# bldcshield.net
KiCad netlist of a schematic drawn in EAGLE
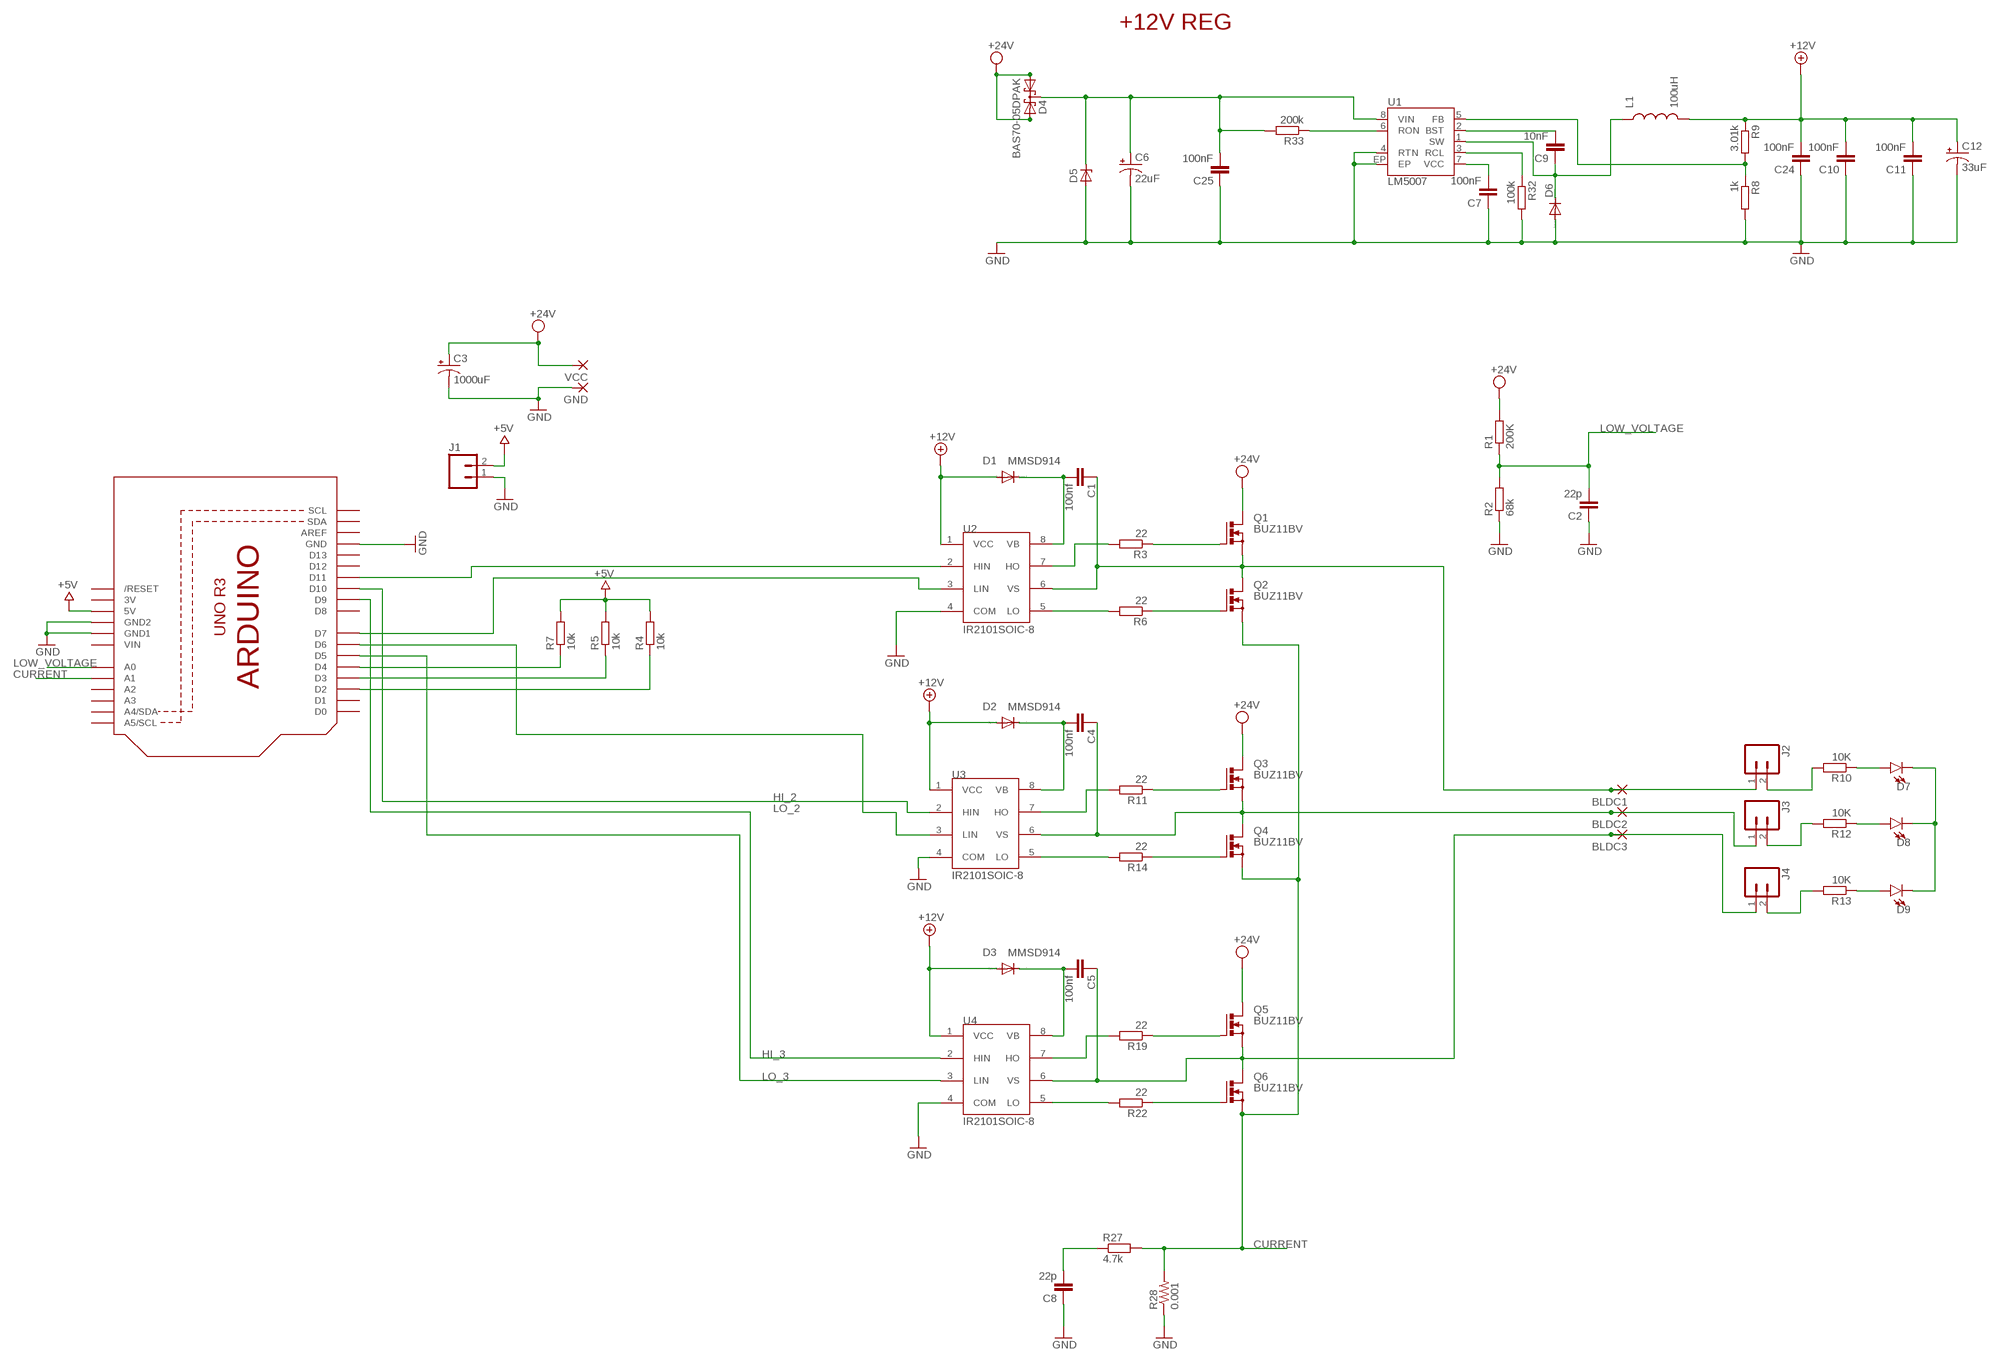
[diagram p0: schematic, sheet 1]

(export (version "E")
  (design (tool "Eeschema 10.0.6"))
  (components
    (comp (ref "BLDC1")
      (value "WIREPAD4,16O1,6")
      (footprint "eagle-import:4,16O1,6")
      (libsource (lib "eagle-import") (part "WIREPAD4,16O1,6"))
    )
    (comp (ref "BLDC2")
      (value "WIREPAD4,16O1,6")
      (footprint "eagle-import:4,16O1,6")
      (libsource (lib "eagle-import") (part "WIREPAD4,16O1,6"))
    )
    (comp (ref "BLDC3")
      (value "WIREPAD4,16O1,6")
      (footprint "eagle-import:4,16O1,6")
      (libsource (lib "eagle-import") (part "WIREPAD4,16O1,6"))
    )
    (comp (ref "C1")
      (value "100nf")
      (footprint "eagle-import:C1206")
      (libsource (lib "eagle-import") (part "C-EUC1206"))
    )
    (comp (ref "C2")
      (value "22p")
      (footprint "eagle-import:C1206")
      (libsource (lib "eagle-import") (part "C-EUC1206"))
    )
    (comp (ref "C3")
      (value "1000uF")
      (footprint "eagle-import:CPOL-RADIAL-1000UF-63V")
      (libsource (lib "eagle-import") (part "CAP_POLPTH3"))
    )
    (comp (ref "C4")
      (value "100nf")
      (footprint "eagle-import:C1206")
      (libsource (lib "eagle-import") (part "C-EUC1206"))
    )
    (comp (ref "C5")
      (value "100nf")
      (footprint "eagle-import:C1206")
      (libsource (lib "eagle-import") (part "C-EUC1206"))
    )
    (comp (ref "C6")
      (value "22uF")
      (footprint "eagle-import:PANASONIC_C")
      (libsource (lib "eagle-import") (part "22UF-POLAR-PANASONIC_C-35V-20%"))
    )
    (comp (ref "C7")
      (value "100nF")
      (footprint "eagle-import:C1206")
      (libsource (lib "eagle-import") (part "C-EUC1206"))
    )
    (comp (ref "C8")
      (value "22p")
      (footprint "eagle-import:C1206")
      (libsource (lib "eagle-import") (part "C-EUC1206"))
    )
    (comp (ref "C9")
      (value "10nF")
      (footprint "eagle-import:C1206")
      (libsource (lib "eagle-import") (part "C-EUC1206"))
    )
    (comp (ref "C10")
      (value "100nF")
      (footprint "eagle-import:C1206")
      (libsource (lib "eagle-import") (part "C-EUC1206"))
    )
    (comp (ref "C11")
      (value "100nF")
      (footprint "eagle-import:C1206")
      (libsource (lib "eagle-import") (part "C-EUC1206"))
    )
    (comp (ref "C12")
      (value "33uF")
      (footprint "eagle-import:PANASONIC_C")
      (libsource (lib "eagle-import") (part "22UF-POLAR-PANASONIC_C-35V-20%"))
    )
    (comp (ref "C24")
      (value "100nF")
      (footprint "eagle-import:C1206")
      (libsource (lib "eagle-import") (part "C-EUC1206"))
    )
    (comp (ref "C25")
      (value "100nF")
      (footprint "eagle-import:C1206")
      (libsource (lib "eagle-import") (part "C-EUC1206"))
    )
    (comp (ref "D1")
      (value "MMSD914")
      (footprint "eagle-import:SOD123")
      (libsource (lib "eagle-import") (part "DIODE-SOD123"))
    )
    (comp (ref "D2")
      (value "MMSD914")
      (footprint "eagle-import:SOD123")
      (libsource (lib "eagle-import") (part "DIODE-SOD123"))
    )
    (comp (ref "D3")
      (value "MMSD914")
      (footprint "eagle-import:SOD123")
      (libsource (lib "eagle-import") (part "DIODE-SOD123"))
    )
    (comp (ref "D4")
      (value "BAS70-05DPAK")
      (footprint "eagle-import:DPAK229P990X238-3N")
      (libsource (lib "eagle-import") (part "BAS70-05DPAK"))
    )
    (comp (ref "D5")
      (value "SMF43A")
      (footprint "eagle-import:SOD123F")
      (fields (field (name "MF") "Littelfuse"))
      (libsource (lib "eagle-import") (part "SMFA43"))
    )
    (comp (ref "D6")
      (value "MBR0520LT")
      (footprint "eagle-import:SOD123")
      (libsource (lib "eagle-import") (part "MBR0520LT"))
    )
    (comp (ref "D7")
      (value "LED5MM")
      (footprint "eagle-import:LED_5MM")
      (libsource (lib "eagle-import") (part "LED5MM"))
    )
    (comp (ref "D8")
      (value "LED5MM")
      (footprint "eagle-import:LED_5MM")
      (libsource (lib "eagle-import") (part "LED5MM"))
    )
    (comp (ref "D9")
      (value "LED5MM")
      (footprint "eagle-import:LED_5MM")
      (libsource (lib "eagle-import") (part "LED5MM"))
    )
    (comp (ref "GND")
      (value "WIREPAD4,16O1,6")
      (footprint "eagle-import:4,16O1,6")
      (libsource (lib "eagle-import") (part "WIREPAD4,16O1,6"))
    )
    (comp (ref "J1")
      (value "M02PTH")
      (footprint "eagle-import:1X02")
      (libsource (lib "eagle-import") (part "M02PTH"))
    )
    (comp (ref "J2")
      (value "M02PTH")
      (footprint "eagle-import:1X02")
      (libsource (lib "eagle-import") (part "M02PTH"))
    )
    (comp (ref "J3")
      (value "M02PTH")
      (footprint "eagle-import:1X02")
      (libsource (lib "eagle-import") (part "M02PTH"))
    )
    (comp (ref "J4")
      (value "M02PTH")
      (footprint "eagle-import:1X02")
      (libsource (lib "eagle-import") (part "M02PTH"))
    )
    (comp (ref "L1")
      (value "100uH")
      (footprint "eagle-import:INDUCTOR-SRP4020")
      (libsource (lib "eagle-import") (part "INDUCTOR"))
    )
    (comp (ref "Q1")
      (value "BUZ11BV")
      (footprint "eagle-import:TO220BV")
      (libsource (lib "eagle-import") (part "BUZ11BV"))
    )
    (comp (ref "Q2")
      (value "BUZ11BV")
      (footprint "eagle-import:TO220BV")
      (libsource (lib "eagle-import") (part "BUZ11BV"))
    )
    (comp (ref "Q3")
      (value "BUZ11BV")
      (footprint "eagle-import:TO220BV")
      (libsource (lib "eagle-import") (part "BUZ11BV"))
    )
    (comp (ref "Q4")
      (value "BUZ11BV")
      (footprint "eagle-import:TO220BV")
      (libsource (lib "eagle-import") (part "BUZ11BV"))
    )
    (comp (ref "Q5")
      (value "BUZ11BV")
      (footprint "eagle-import:TO220BV")
      (libsource (lib "eagle-import") (part "BUZ11BV"))
    )
    (comp (ref "Q6")
      (value "BUZ11BV")
      (footprint "eagle-import:TO220BV")
      (libsource (lib "eagle-import") (part "BUZ11BV"))
    )
    (comp (ref "Q8")
      (value "Shield")
      (footprint "eagle-import:ARDUINOR3-NOTEXT-NOIOREF")
      (libsource (lib "eagle-import") (part "ARDUINOR3-NOIOREF-NOTEXT"))
    )
    (comp (ref "R1")
      (value "200K")
      (footprint "eagle-import:R1206")
      (libsource (lib "eagle-import") (part "R-EU_R1206"))
    )
    (comp (ref "R2")
      (value "68k")
      (footprint "eagle-import:R1206")
      (libsource (lib "eagle-import") (part "R-EU_R1206"))
    )
    (comp (ref "R3")
      (value "22")
      (footprint "eagle-import:R1206")
      (libsource (lib "eagle-import") (part "R-EU_R1206"))
    )
    (comp (ref "R4")
      (value "10k")
      (footprint "eagle-import:R1206")
      (libsource (lib "eagle-import") (part "R-EU_R1206"))
    )
    (comp (ref "R5")
      (value "10k")
      (footprint "eagle-import:R1206")
      (libsource (lib "eagle-import") (part "R-EU_R1206"))
    )
    (comp (ref "R6")
      (value "22")
      (footprint "eagle-import:R1206")
      (libsource (lib "eagle-import") (part "R-EU_R1206"))
    )
    (comp (ref "R7")
      (value "10k")
      (footprint "eagle-import:R1206")
      (libsource (lib "eagle-import") (part "R-EU_R1206"))
    )
    (comp (ref "R8")
      (value "1k")
      (footprint "eagle-import:R1206")
      (libsource (lib "eagle-import") (part "R-EU_R1206"))
    )
    (comp (ref "R9")
      (value "3.01k")
      (footprint "eagle-import:R1206")
      (libsource (lib "eagle-import") (part "R-EU_R1206"))
    )
    (comp (ref "R10")
      (value "10K")
      (footprint "eagle-import:R1206")
      (libsource (lib "eagle-import") (part "R-EU_R1206"))
    )
    (comp (ref "R11")
      (value "22")
      (footprint "eagle-import:R1206")
      (libsource (lib "eagle-import") (part "R-EU_R1206"))
    )
    (comp (ref "R12")
      (value "10K")
      (footprint "eagle-import:R1206")
      (libsource (lib "eagle-import") (part "R-EU_R1206"))
    )
    (comp (ref "R13")
      (value "10K")
      (footprint "eagle-import:R1206")
      (libsource (lib "eagle-import") (part "R-EU_R1206"))
    )
    (comp (ref "R14")
      (value "22")
      (footprint "eagle-import:R1206")
      (libsource (lib "eagle-import") (part "R-EU_R1206"))
    )
    (comp (ref "R19")
      (value "22")
      (footprint "eagle-import:R1206")
      (libsource (lib "eagle-import") (part "R-EU_R1206"))
    )
    (comp (ref "R22")
      (value "22")
      (footprint "eagle-import:R1206")
      (libsource (lib "eagle-import") (part "R-EU_R1206"))
    )
    (comp (ref "R27")
      (value "4.7k")
      (footprint "eagle-import:R1206")
      (libsource (lib "eagle-import") (part "R-EU_R1206"))
    )
    (comp (ref "R28")
      (value "0.001")
      (footprint "eagle-import:R2512")
      (libsource (lib "eagle-import") (part "R-US_R2512"))
    )
    (comp (ref "R32")
      (value "100k")
      (footprint "eagle-import:R1206")
      (libsource (lib "eagle-import") (part "R-EU_R1206"))
    )
    (comp (ref "R33")
      (value "200k")
      (footprint "eagle-import:R1206")
      (libsource (lib "eagle-import") (part "R-EU_R1206"))
    )
    (comp (ref "U1")
      (value "LM5007")
      (footprint "eagle-import:MSOP-8-EP")
      (libsource (lib "eagle-import") (part "LM5007"))
    )
    (comp (ref "U2")
      (value "IR2101SOIC-8")
      (footprint "eagle-import:SOIC127P490X600X175-8N")
      (libsource (lib "eagle-import") (part "IR2101SOIC-8"))
    )
    (comp (ref "U3")
      (value "IR2101SOIC-8")
      (footprint "eagle-import:SOIC127P490X600X175-8N")
      (libsource (lib "eagle-import") (part "IR2101SOIC-8"))
    )
    (comp (ref "U4")
      (value "IR2101SOIC-8")
      (footprint "eagle-import:SOIC127P490X600X175-8N")
      (libsource (lib "eagle-import") (part "IR2101SOIC-8"))
    )
    (comp (ref "VCC")
      (value "WIREPAD4,16O1,6")
      (footprint "eagle-import:4,16O1,6")
      (libsource (lib "eagle-import") (part "WIREPAD4,16O1,6"))
    )
  )
  (nets
    (net (code "1") (name "+5V") (class "Default")
      (node (ref "J1") (pin "2") (pinfunction "2_2") (pintype "passive"))
      (node (ref "Q8") (pin "5V") (pinfunction "5V_5V") (pintype "power_in"))
      (node (ref "R4") (pin "2") (pinfunction "2_2") (pintype "passive"))
      (node (ref "R5") (pin "2") (pinfunction "2_2") (pintype "passive"))
      (node (ref "R7") (pin "2") (pinfunction "2_2") (pintype "passive"))
    )
    (net (code "2") (name "+12V") (class "Default")
      (node (ref "C10") (pin "2") (pinfunction "2_2") (pintype "passive"))
      (node (ref "C11") (pin "2") (pinfunction "2_2") (pintype "passive"))
      (node (ref "C12") (pin "+") (pinfunction "+_+") (pintype "passive"))
      (node (ref "C24") (pin "2") (pinfunction "2_2") (pintype "passive"))
      (node (ref "D1") (pin "A") (pinfunction "A_A") (pintype "passive"))
      (node (ref "D2") (pin "A") (pinfunction "A_A") (pintype "passive"))
      (node (ref "D3") (pin "A") (pinfunction "A_A") (pintype "passive"))
      (node (ref "L1") (pin "P$2") (pinfunction "2_P$2") (pintype "passive"))
      (node (ref "R9") (pin "1") (pinfunction "1_1") (pintype "passive"))
      (node (ref "U2") (pin "1") (pinfunction "VCC_1") (pintype "power_in"))
      (node (ref "U3") (pin "1") (pinfunction "VCC_1") (pintype "power_in"))
      (node (ref "U4") (pin "1") (pinfunction "VCC_1") (pintype "power_in"))
    )
    (net (code "3") (name "+24V") (class "Default")
      (node (ref "C3") (pin "1") (pinfunction "+_1") (pintype "passive"))
      (node (ref "D4") (pin "1") (pinfunction "A1_1") (pintype "passive"))
      (node (ref "D4") (pin "3") (pinfunction "A2_3") (pintype "passive"))
      (node (ref "Q1") (pin "D") (pinfunction "D_D") (pintype "passive"))
      (node (ref "Q3") (pin "D") (pinfunction "D_D") (pintype "passive"))
      (node (ref "Q5") (pin "D") (pinfunction "D_D") (pintype "passive"))
      (node (ref "R1") (pin "2") (pinfunction "2_2") (pintype "passive"))
      (node (ref "VCC") (pin "1") (pinfunction "P_1") (pintype "passive"))
    )
    (net (code "4") (name "/3V") (class "Default")
      (node (ref "Q8") (pin "3V") (pinfunction "3V_3V") (pintype "power_in"))
    )
    (net (code "5") (name "/CURRENT") (class "Default")
      (node (ref "Q2") (pin "S") (pinfunction "S_S") (pintype "passive"))
      (node (ref "Q4") (pin "S") (pinfunction "S_S") (pintype "passive"))
      (node (ref "Q6") (pin "S") (pinfunction "S_S") (pintype "passive"))
      (node (ref "Q8") (pin "A1") (pinfunction "A1_A1") (pintype "bidirectional"))
      (node (ref "R27") (pin "2") (pinfunction "2_2") (pintype "passive"))
      (node (ref "R28") (pin "2") (pinfunction "2_2") (pintype "passive"))
    )
    (net (code "6") (name "/HI_2") (class "Default")
      (node (ref "Q8") (pin "D10") (pinfunction "D10_D10") (pintype "bidirectional"))
      (node (ref "U3") (pin "2") (pinfunction "HIN_2") (pintype "input"))
    )
    (net (code "7") (name "/HI_3") (class "Default")
      (node (ref "Q8") (pin "D9") (pinfunction "D9_D9") (pintype "bidirectional"))
      (node (ref "U4") (pin "2") (pinfunction "HIN_2") (pintype "input"))
    )
    (net (code "8") (name "/LOW_VOLTAGE") (class "Default")
      (node (ref "C2") (pin "2") (pinfunction "2_2") (pintype "passive"))
      (node (ref "Q8") (pin "A0") (pinfunction "A0_A0") (pintype "bidirectional"))
      (node (ref "R1") (pin "1") (pinfunction "1_1") (pintype "passive"))
      (node (ref "R2") (pin "2") (pinfunction "2_2") (pintype "passive"))
    )
    (net (code "9") (name "/LO_2") (class "Default")
      (node (ref "Q8") (pin "D6") (pinfunction "D6_D6") (pintype "bidirectional"))
      (node (ref "U3") (pin "3") (pinfunction "LIN_3") (pintype "input"))
    )
    (net (code "10") (name "/LO_3") (class "Default")
      (node (ref "Q8") (pin "D5") (pinfunction "D5_D5") (pintype "bidirectional"))
      (node (ref "U4") (pin "3") (pinfunction "LIN_3") (pintype "input"))
    )
    (net (code "11") (name "/VIN") (class "Default")
      (node (ref "Q8") (pin "VIN") (pinfunction "VIN_VIN") (pintype "power_in"))
    )
    (net (code "12") (name "GND") (class "Default")
      (node (ref "C10") (pin "1") (pinfunction "1_1") (pintype "passive"))
      (node (ref "C11") (pin "1") (pinfunction "1_1") (pintype "passive"))
      (node (ref "C12") (pin "-") (pinfunction "-_-") (pintype "passive"))
      (node (ref "C2") (pin "1") (pinfunction "1_1") (pintype "passive"))
      (node (ref "C24") (pin "1") (pinfunction "1_1") (pintype "passive"))
      (node (ref "C25") (pin "1") (pinfunction "1_1") (pintype "passive"))
      (node (ref "C3") (pin "2") (pinfunction "-_2") (pintype "passive"))
      (node (ref "C6") (pin "-") (pinfunction "-_-") (pintype "passive"))
      (node (ref "C7") (pin "1") (pinfunction "1_1") (pintype "passive"))
      (node (ref "C8") (pin "1") (pinfunction "1_1") (pintype "passive"))
      (node (ref "D5") (pin "A") (pinfunction "A_A") (pintype "passive"))
      (node (ref "D6") (pin "A") (pinfunction "A_A") (pintype "passive"))
      (node (ref "GND") (pin "1") (pinfunction "P_1") (pintype "passive"))
      (node (ref "J1") (pin "1") (pinfunction "1_1") (pintype "passive"))
      (node (ref "Q8") (pin "GND") (pinfunction "GND_GND") (pintype "power_in"))
      (node (ref "Q8") (pin "GND1") (pinfunction "GND1_GND1") (pintype "power_in"))
      (node (ref "Q8") (pin "GND2") (pinfunction "GND2_GND2") (pintype "power_in"))
      (node (ref "R2") (pin "1") (pinfunction "1_1") (pintype "passive"))
      (node (ref "R28") (pin "1") (pinfunction "1_1") (pintype "passive"))
      (node (ref "R32") (pin "2") (pinfunction "2_2") (pintype "passive"))
      (node (ref "R8") (pin "2") (pinfunction "2_2") (pintype "passive"))
      (node (ref "U1") (pin "4") (pinfunction "RTN_4") (pintype "bidirectional"))
      (node (ref "U1") (pin "EP") (pinfunction "EP_EP") (pintype "bidirectional"))
      (node (ref "U2") (pin "4") (pinfunction "COM_4") (pintype "power_in"))
      (node (ref "U3") (pin "4") (pinfunction "COM_4") (pintype "power_in"))
      (node (ref "U4") (pin "4") (pinfunction "COM_4") (pintype "power_in"))
    )
    (net (code "13") (name "Net-(BLDC1-P)") (class "Default")
      (node (ref "BLDC1") (pin "1") (pinfunction "P_1") (pintype "passive"))
      (node (ref "C1") (pin "1") (pinfunction "1_1") (pintype "passive"))
      (node (ref "J2") (pin "1") (pinfunction "1_1") (pintype "passive"))
      (node (ref "Q1") (pin "S") (pinfunction "S_S") (pintype "passive"))
      (node (ref "Q2") (pin "D") (pinfunction "D_D") (pintype "passive"))
      (node (ref "U2") (pin "6") (pinfunction "VS_6") (pintype "output"))
    )
    (net (code "14") (name "Net-(BLDC2-P)") (class "Default")
      (node (ref "BLDC2") (pin "1") (pinfunction "P_1") (pintype "passive"))
      (node (ref "C4") (pin "1") (pinfunction "1_1") (pintype "passive"))
      (node (ref "J3") (pin "1") (pinfunction "1_1") (pintype "passive"))
      (node (ref "Q3") (pin "S") (pinfunction "S_S") (pintype "passive"))
      (node (ref "Q4") (pin "D") (pinfunction "D_D") (pintype "passive"))
      (node (ref "U3") (pin "6") (pinfunction "VS_6") (pintype "output"))
    )
    (net (code "15") (name "Net-(BLDC3-P)") (class "Default")
      (node (ref "BLDC3") (pin "1") (pinfunction "P_1") (pintype "passive"))
      (node (ref "C5") (pin "1") (pinfunction "1_1") (pintype "passive"))
      (node (ref "J4") (pin "1") (pinfunction "1_1") (pintype "passive"))
      (node (ref "Q5") (pin "S") (pinfunction "S_S") (pintype "passive"))
      (node (ref "Q6") (pin "D") (pinfunction "D_D") (pintype "passive"))
      (node (ref "U4") (pin "6") (pinfunction "VS_6") (pintype "output"))
    )
    (net (code "16") (name "Net-(C8-Pad2)") (class "Default")
      (node (ref "C8") (pin "2") (pinfunction "2_2") (pintype "passive"))
      (node (ref "R27") (pin "1") (pinfunction "1_1") (pintype "passive"))
    )
    (net (code "17") (name "Net-(D4-K1K2)") (class "Default")
      (node (ref "C25") (pin "2") (pinfunction "2_2") (pintype "passive"))
      (node (ref "C6") (pin "+") (pinfunction "+_+") (pintype "passive"))
      (node (ref "D4") (pin "4") (pinfunction "K1K2_4") (pintype "passive"))
      (node (ref "D5") (pin "C") (pinfunction "C_C") (pintype "passive"))
      (node (ref "R33") (pin "2") (pinfunction "2_2") (pintype "passive"))
      (node (ref "U1") (pin "8") (pinfunction "VIN_8") (pintype "bidirectional"))
    )
    (net (code "18") (name "Net-(D7-C)") (class "Default")
      (node (ref "D7") (pin "K") (pinfunction "C_K") (pintype "passive"))
      (node (ref "D8") (pin "K") (pinfunction "C_K") (pintype "passive"))
      (node (ref "D9") (pin "K") (pinfunction "C_K") (pintype "passive"))
    )
    (net (code "19") (name "Net-(D7-PadA)") (class "Default")
      (node (ref "D7") (pin "A") (pinfunction "A_A") (pintype "passive"))
      (node (ref "R10") (pin "1") (pinfunction "1_1") (pintype "passive"))
    )
    (net (code "20") (name "Net-(D8-PadA)") (class "Default")
      (node (ref "D8") (pin "A") (pinfunction "A_A") (pintype "passive"))
      (node (ref "R12") (pin "1") (pinfunction "1_1") (pintype "passive"))
    )
    (net (code "21") (name "Net-(D9-PadA)") (class "Default")
      (node (ref "D9") (pin "A") (pinfunction "A_A") (pintype "passive"))
      (node (ref "R13") (pin "1") (pinfunction "1_1") (pintype "passive"))
    )
    (net (code "22") (name "Net-(J2-Pad2)") (class "Default")
      (node (ref "J2") (pin "2") (pinfunction "2_2") (pintype "passive"))
      (node (ref "R10") (pin "2") (pinfunction "2_2") (pintype "passive"))
    )
    (net (code "23") (name "Net-(J3-Pad2)") (class "Default")
      (node (ref "J3") (pin "2") (pinfunction "2_2") (pintype "passive"))
      (node (ref "R12") (pin "2") (pinfunction "2_2") (pintype "passive"))
    )
    (net (code "24") (name "Net-(J4-Pad2)") (class "Default")
      (node (ref "J4") (pin "2") (pinfunction "2_2") (pintype "passive"))
      (node (ref "R13") (pin "2") (pinfunction "2_2") (pintype "passive"))
    )
    (net (code "25") (name "Net-(L1-1)") (class "Default")
      (node (ref "C9") (pin "1") (pinfunction "1_1") (pintype "passive"))
      (node (ref "D6") (pin "C") (pinfunction "C_C") (pintype "passive"))
      (node (ref "L1") (pin "P$1") (pinfunction "1_P$1") (pintype "passive"))
      (node (ref "U1") (pin "1") (pinfunction "SW_1") (pintype "bidirectional"))
    )
    (net (code "26") (name "Net-(Q1-PadG)") (class "Default")
      (node (ref "Q1") (pin "G") (pinfunction "G_G") (pintype "passive"))
      (node (ref "R3") (pin "1") (pinfunction "1_1") (pintype "passive"))
    )
    (net (code "27") (name "Net-(Q2-PadG)") (class "Default")
      (node (ref "Q2") (pin "G") (pinfunction "G_G") (pintype "passive"))
      (node (ref "R6") (pin "1") (pinfunction "1_1") (pintype "passive"))
    )
    (net (code "28") (name "Net-(Q3-PadG)") (class "Default")
      (node (ref "Q3") (pin "G") (pinfunction "G_G") (pintype "passive"))
      (node (ref "R11") (pin "1") (pinfunction "1_1") (pintype "passive"))
    )
    (net (code "29") (name "Net-(Q4-PadG)") (class "Default")
      (node (ref "Q4") (pin "G") (pinfunction "G_G") (pintype "passive"))
      (node (ref "R14") (pin "1") (pinfunction "1_1") (pintype "passive"))
    )
    (net (code "30") (name "Net-(Q5-PadG)") (class "Default")
      (node (ref "Q5") (pin "G") (pinfunction "G_G") (pintype "passive"))
      (node (ref "R19") (pin "1") (pinfunction "1_1") (pintype "passive"))
    )
    (net (code "31") (name "Net-(Q6-PadG)") (class "Default")
      (node (ref "Q6") (pin "G") (pinfunction "G_G") (pintype "passive"))
      (node (ref "R22") (pin "1") (pinfunction "1_1") (pintype "passive"))
    )
    (net (code "32") (name "Net-(Q8-PadD2)") (class "Default")
      (node (ref "Q8") (pin "D2") (pinfunction "D2_D2") (pintype "bidirectional"))
      (node (ref "R4") (pin "1") (pinfunction "1_1") (pintype "passive"))
    )
    (net (code "33") (name "Net-(Q8-PadD3)") (class "Default")
      (node (ref "Q8") (pin "D3") (pinfunction "D3_D3") (pintype "bidirectional"))
      (node (ref "R5") (pin "1") (pinfunction "1_1") (pintype "passive"))
    )
    (net (code "34") (name "Net-(Q8-PadD4)") (class "Default")
      (node (ref "Q8") (pin "D4") (pinfunction "D4_D4") (pintype "bidirectional"))
      (node (ref "R7") (pin "1") (pinfunction "1_1") (pintype "passive"))
    )
    (net (code "35") (name "Net-(U1-BST)") (class "Default")
      (node (ref "C9") (pin "2") (pinfunction "2_2") (pintype "passive"))
      (node (ref "U1") (pin "2") (pinfunction "BST_2") (pintype "bidirectional"))
    )
    (net (code "36") (name "Net-(U1-FB)") (class "Default")
      (node (ref "R8") (pin "1") (pinfunction "1_1") (pintype "passive"))
      (node (ref "R9") (pin "2") (pinfunction "2_2") (pintype "passive"))
      (node (ref "U1") (pin "5") (pinfunction "FB_5") (pintype "bidirectional"))
    )
    (net (code "37") (name "Net-(U1-RCL)") (class "Default")
      (node (ref "R32") (pin "1") (pinfunction "1_1") (pintype "passive"))
      (node (ref "U1") (pin "3") (pinfunction "RCL_3") (pintype "bidirectional"))
    )
    (net (code "38") (name "Net-(U1-RON)") (class "Default")
      (node (ref "R33") (pin "1") (pinfunction "1_1") (pintype "passive"))
      (node (ref "U1") (pin "6") (pinfunction "RON_6") (pintype "bidirectional"))
    )
    (net (code "39") (name "Net-(U1-VCC)") (class "Default")
      (node (ref "C7") (pin "2") (pinfunction "2_2") (pintype "passive"))
      (node (ref "U1") (pin "7") (pinfunction "VCC_7") (pintype "bidirectional"))
    )
    (net (code "40") (name "Net-(U2-HIN)") (class "Default")
      (node (ref "Q8") (pin "D11") (pinfunction "D11_D11") (pintype "bidirectional"))
      (node (ref "U2") (pin "2") (pinfunction "HIN_2") (pintype "input"))
    )
    (net (code "41") (name "Net-(U2-HO)") (class "Default")
      (node (ref "R3") (pin "2") (pinfunction "2_2") (pintype "passive"))
      (node (ref "U2") (pin "7") (pinfunction "HO_7") (pintype "output"))
    )
    (net (code "42") (name "Net-(U2-LIN)") (class "Default")
      (node (ref "Q8") (pin "D7") (pinfunction "D7_D7") (pintype "bidirectional"))
      (node (ref "U2") (pin "3") (pinfunction "LIN_3") (pintype "input"))
    )
    (net (code "43") (name "Net-(U2-LO)") (class "Default")
      (node (ref "R6") (pin "2") (pinfunction "2_2") (pintype "passive"))
      (node (ref "U2") (pin "5") (pinfunction "LO_5") (pintype "output"))
    )
    (net (code "44") (name "Net-(U2-VB)") (class "Default")
      (node (ref "C1") (pin "2") (pinfunction "2_2") (pintype "passive"))
      (node (ref "D1") (pin "C") (pinfunction "C_C") (pintype "passive"))
      (node (ref "U2") (pin "8") (pinfunction "VB_8") (pintype "power_in"))
    )
    (net (code "45") (name "Net-(U3-HO)") (class "Default")
      (node (ref "R11") (pin "2") (pinfunction "2_2") (pintype "passive"))
      (node (ref "U3") (pin "7") (pinfunction "HO_7") (pintype "output"))
    )
    (net (code "46") (name "Net-(U3-LO)") (class "Default")
      (node (ref "R14") (pin "2") (pinfunction "2_2") (pintype "passive"))
      (node (ref "U3") (pin "5") (pinfunction "LO_5") (pintype "output"))
    )
    (net (code "47") (name "Net-(U3-VB)") (class "Default")
      (node (ref "C4") (pin "2") (pinfunction "2_2") (pintype "passive"))
      (node (ref "D2") (pin "C") (pinfunction "C_C") (pintype "passive"))
      (node (ref "U3") (pin "8") (pinfunction "VB_8") (pintype "power_in"))
    )
    (net (code "48") (name "Net-(U4-HO)") (class "Default")
      (node (ref "R19") (pin "2") (pinfunction "2_2") (pintype "passive"))
      (node (ref "U4") (pin "7") (pinfunction "HO_7") (pintype "output"))
    )
    (net (code "49") (name "Net-(U4-LO)") (class "Default")
      (node (ref "R22") (pin "2") (pinfunction "2_2") (pintype "passive"))
      (node (ref "U4") (pin "5") (pinfunction "LO_5") (pintype "output"))
    )
    (net (code "50") (name "Net-(U4-VB)") (class "Default")
      (node (ref "C5") (pin "2") (pinfunction "2_2") (pintype "passive"))
      (node (ref "D3") (pin "C") (pinfunction "C_C") (pintype "passive"))
      (node (ref "U4") (pin "8") (pinfunction "VB_8") (pintype "power_in"))
    )
    (net (code "51") (name "unconnected-(Q8-A4{slash}SDA-PadA4)") (class "Default")
      (node (ref "Q8") (pin "A4") (pinfunction "A4/SDA_A4") (pintype "bidirectional"))
    )
    (net (code "52") (name "unconnected-(Q8-A5{slash}SCL-PadA5)") (class "Default")
      (node (ref "Q8") (pin "A5") (pinfunction "A5/SCL_A5") (pintype "bidirectional"))
    )
    (net (code "53") (name "unconnected-(Q8-PadA2)") (class "Default")
      (node (ref "Q8") (pin "A2") (pinfunction "A2_A2") (pintype "bidirectional"))
    )
    (net (code "54") (name "unconnected-(Q8-PadA3)") (class "Default")
      (node (ref "Q8") (pin "A3") (pinfunction "A3_A3") (pintype "bidirectional"))
    )
    (net (code "55") (name "unconnected-(Q8-PadAREF)") (class "Default")
      (node (ref "Q8") (pin "AREF") (pinfunction "AREF_AREF") (pintype "bidirectional"))
    )
    (net (code "56") (name "unconnected-(Q8-PadD0)") (class "Default")
      (node (ref "Q8") (pin "D0") (pinfunction "D0_D0") (pintype "bidirectional"))
    )
    (net (code "57") (name "unconnected-(Q8-PadD1)") (class "Default")
      (node (ref "Q8") (pin "D1") (pinfunction "D1_D1") (pintype "bidirectional"))
    )
    (net (code "58") (name "unconnected-(Q8-PadD8)") (class "Default")
      (node (ref "Q8") (pin "D8") (pinfunction "D8_D8") (pintype "bidirectional"))
    )
    (net (code "59") (name "unconnected-(Q8-PadD12)") (class "Default")
      (node (ref "Q8") (pin "D12") (pinfunction "D12_D12") (pintype "bidirectional"))
    )
    (net (code "60") (name "unconnected-(Q8-PadD13)") (class "Default")
      (node (ref "Q8") (pin "D13") (pinfunction "D13_D13") (pintype "bidirectional"))
    )
    (net (code "61") (name "unconnected-(Q8-PadSCL)") (class "Default")
      (node (ref "Q8") (pin "SCL") (pinfunction "SCL_SCL") (pintype "bidirectional"))
    )
    (net (code "62") (name "unconnected-(Q8-PadSDA)") (class "Default")
      (node (ref "Q8") (pin "SDA") (pinfunction "SDA_SDA") (pintype "bidirectional"))
    )
    (net (code "63") (name "unconnected-(Q8-{slash}RESET-PadRESET)") (class "Default")
      (node (ref "Q8") (pin "RESET") (pinfunction "/RESET_RESET") (pintype "bidirectional"))
    )
  )
)
